# PX4FMUv2_4_6_10.net
KiCad netlist of a schematic drawn in Altium Designer
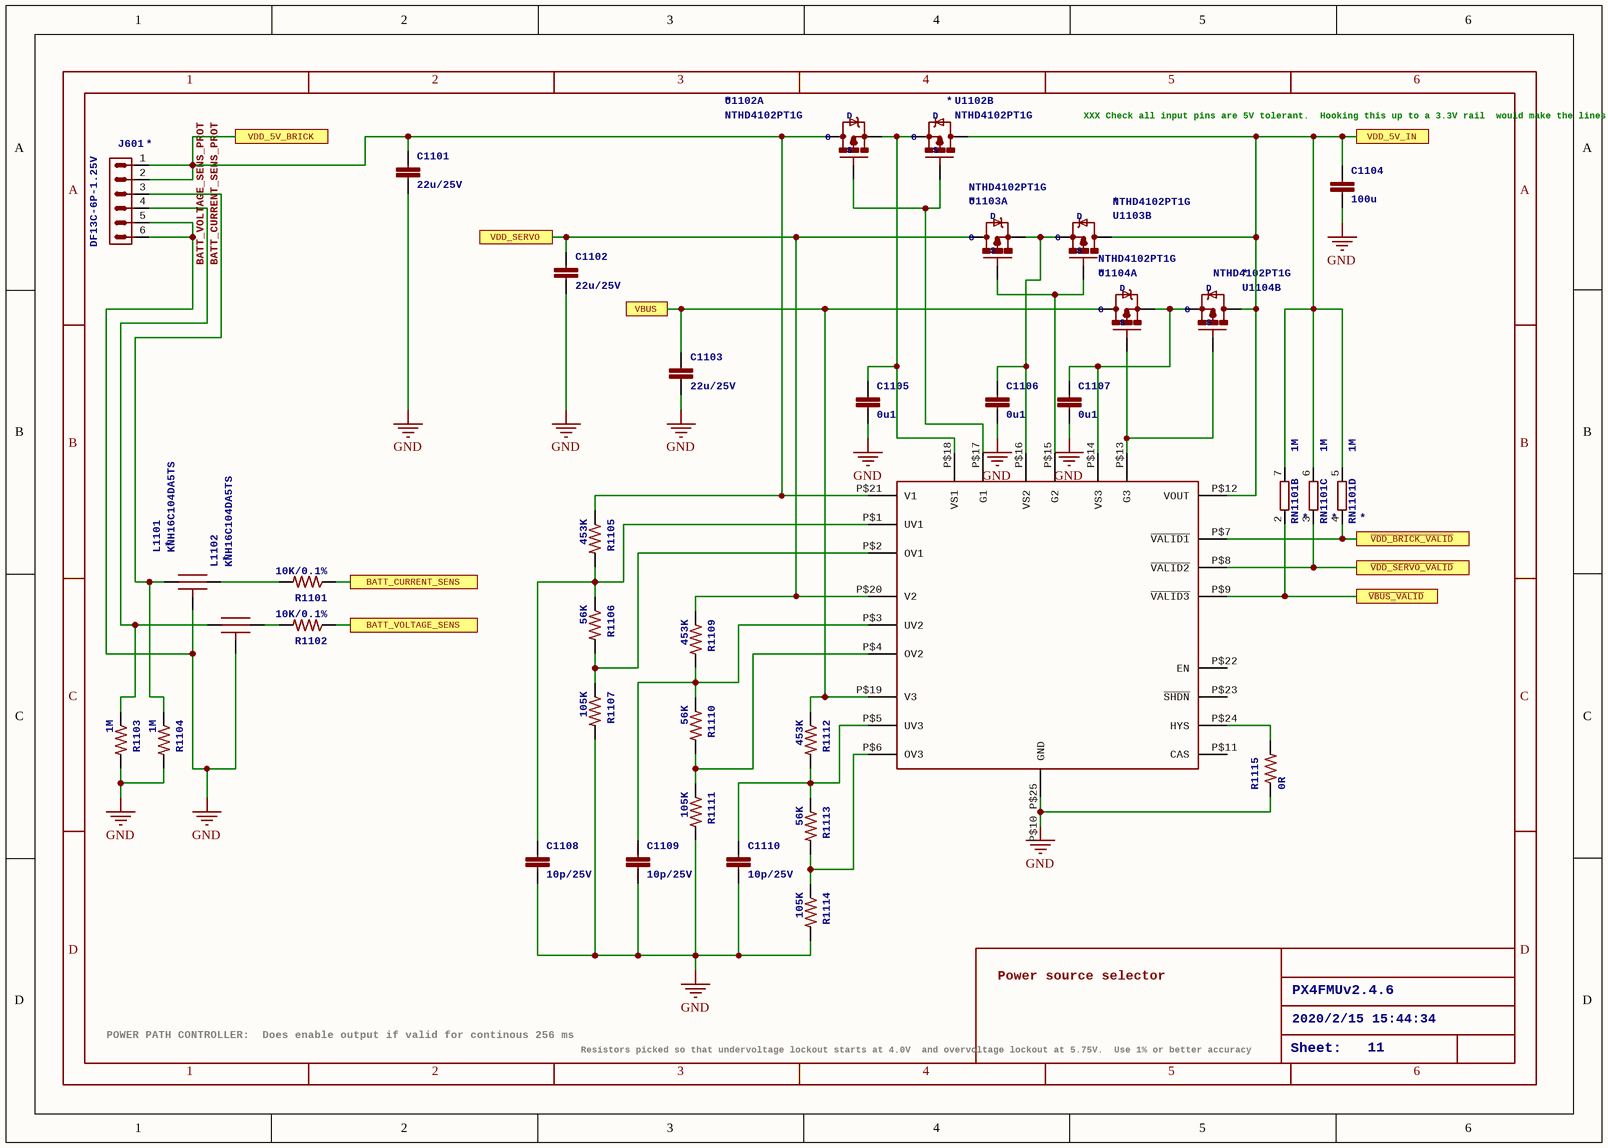
[diagram p0: PX4FMUv2.4.6_10.SchDoc]

(export (version "E")
  (design (tool "Eeschema 10.0.6"))
  (components
    (comp (ref "C1101")
      (value "22u/25V")
      (footprint "0805-CAP")
      (description "CapacitorStandard 0603 ceramic capacitor, and 0.1\" leaded capacitor.")
      (fields (field (name "PARTNO") "CL21A226MAQNNNE"))
      (libsource (lib "pixhawk2") (part "CAP0805"))
    )
    (comp (ref "C1102")
      (value "22u/25V")
      (footprint "0805-CAP")
      (description "CapacitorStandard 0603 ceramic capacitor, and 0.1\" leaded capacitor.")
      (fields (field (name "PARTNO") "CL21A226MAQNNNE"))
      (libsource (lib "pixhawk2") (part "CAP0805"))
    )
    (comp (ref "C1103")
      (value "22u/25V")
      (footprint "0805-CAP")
      (description "CapacitorStandard 0603 ceramic capacitor, and 0.1\" leaded capacitor.")
      (fields (field (name "PARTNO") "CL21A226MAQNNNE"))
      (libsource (lib "pixhawk2") (part "CAP0805"))
    )
    (comp (ref "C1104")
      (value "100u")
      (footprint "1206-CAP")
      (description "CapacitorStandard 0603 ceramic capacitor, and 0.1\" leaded capacitor.")
      (fields (field (name "PARTNO") "C3216X5R1A107M160AC"))
      (libsource (lib "pixhawk2") (part "CAP1206"))
    )
    (comp (ref "C1105")
      (value "0u1")
      (footprint "0402-CAP")
      (description "CapacitorStandard 0603 ceramic capacitor, and 0.1\" leaded capacitor.")
      (fields (field (name "PARTNO") "C1005X7R1E104K050BB"))
      (libsource (lib "pixhawk2") (part "CAP0402"))
    )
    (comp (ref "C1106")
      (value "0u1")
      (footprint "0402-CAP")
      (description "CapacitorStandard 0603 ceramic capacitor, and 0.1\" leaded capacitor.")
      (fields (field (name "PARTNO") "C1005X7R1E104K050BB"))
      (libsource (lib "pixhawk2") (part "CAP0402"))
    )
    (comp (ref "C1107")
      (value "0u1")
      (footprint "0402-CAP")
      (description "CapacitorStandard 0603 ceramic capacitor, and 0.1\" leaded capacitor.")
      (fields (field (name "PARTNO") "C1005X7R1E104K050BB"))
      (libsource (lib "pixhawk2") (part "CAP0402"))
    )
    (comp (ref "C1108")
      (value "10p/25V")
      (footprint "0402-CAP")
      (description "CapacitorStandard 0603 ceramic capacitor, and 0.1\" leaded capacitor.")
      (fields (field (name "PARTNO") "C0402C100J3GACTU"))
      (libsource (lib "pixhawk2") (part "CAP0402"))
    )
    (comp (ref "C1109")
      (value "10p/25V")
      (footprint "0402-CAP")
      (description "CapacitorStandard 0603 ceramic capacitor, and 0.1\" leaded capacitor.")
      (fields (field (name "PARTNO") "C0402C100J3GACTU"))
      (libsource (lib "pixhawk2") (part "CAP0402"))
    )
    (comp (ref "C1110")
      (value "10p/25V")
      (footprint "0402-CAP")
      (description "CapacitorStandard 0603 ceramic capacitor, and 0.1\" leaded capacitor.")
      (fields (field (name "PARTNO") "C0402C100J3GACTU"))
      (libsource (lib "pixhawk2") (part "CAP0402"))
    )
    (comp (ref "J601")
      (value "DF13C-6P-1.25V")
      (footprint "DF13C-6P-1.25V")
      (description "DF13-6P 1.25mm Pitch Miniature Crimping Connector.")
      (fields
        (field (name "NAME") "*")
        (field (name "PARTNO") "DF13C-6P-1.25V(20)")
        (field (name "LIBRARYNAME") "con-hirose-df13")
      )
      (libsource (lib "con-hirose-df13") (part "DF13-6P-1.25V"))
    )
    (comp (ref "L1101")
      (value "KNH16C104DA5TS")
      (footprint "KYOCERA-KNH16-DA")
      (description "Kyocera KNH16C104DA5TS EMI filter")
      (fields (field (name "NAME") "*"))
      (libsource (lib "pixhawk2") (part "KNH16C104DA5TS"))
    )
    (comp (ref "L1102")
      (value "KNH16C104DA5TS")
      (footprint "KYOCERA-KNH16-DA")
      (description "Kyocera KNH16C104DA5TS EMI filter")
      (fields (field (name "NAME") "*"))
      (libsource (lib "pixhawk2") (part "KNH16C104DA5TS"))
    )
    (comp (ref "R1101")
      (value "10K/0.1%")
      (footprint "0402-RES")
      (fields (field (name "PARTNO") "ERA-2AEB103X"))
      (libsource (lib "pixhawk2") (part "RESISTOR0402-RES"))
    )
    (comp (ref "R1102")
      (value "10K/0.1%")
      (footprint "0402-RES")
      (fields (field (name "PARTNO") "ERA-2AEB103X"))
      (libsource (lib "pixhawk2") (part "RESISTOR0402-RES"))
    )
    (comp (ref "R1103")
      (value "1M")
      (footprint "0402-RES")
      (fields (field (name "PARTNO") "RC0402FR-071ML"))
      (libsource (lib "pixhawk2") (part "RESISTOR0402-RES"))
    )
    (comp (ref "R1104")
      (value "1M")
      (footprint "0402-RES")
      (fields (field (name "PARTNO") "RC0402FR-071ML"))
      (libsource (lib "pixhawk2") (part "RESISTOR0402-RES"))
    )
    (comp (ref "R1105")
      (value "453K")
      (footprint "0402-RES")
      (fields (field (name "PARTNO") "RMCF0402FT453K"))
      (libsource (lib "pixhawk2") (part "RESISTOR0402-RES"))
    )
    (comp (ref "R1106")
      (value "56K")
      (footprint "0402-RES")
      (fields (field (name "PARTNO") "ERA-2AEB563X"))
      (libsource (lib "pixhawk2") (part "RESISTOR0402-RES"))
    )
    (comp (ref "R1107")
      (value "105K")
      (footprint "0402-RES")
      (fields (field (name "PARTNO") "ERJ-2RKF1053X"))
      (libsource (lib "pixhawk2") (part "RESISTOR0402-RES"))
    )
    (comp (ref "R1109")
      (value "453K")
      (footprint "0402-RES")
      (fields (field (name "PARTNO") "RMCF0402FT453K"))
      (libsource (lib "pixhawk2") (part "RESISTOR0402-RES"))
    )
    (comp (ref "R1110")
      (value "56K")
      (footprint "0402-RES")
      (fields (field (name "PARTNO") "ERA-2AEB563X"))
      (libsource (lib "pixhawk2") (part "RESISTOR0402-RES"))
    )
    (comp (ref "R1111")
      (value "105K")
      (footprint "0402-RES")
      (fields (field (name "PARTNO") "ERJ-2RKF1053X"))
      (libsource (lib "pixhawk2") (part "RESISTOR0402-RES"))
    )
    (comp (ref "R1112")
      (value "453K")
      (footprint "0402-RES")
      (fields (field (name "PARTNO") "RMCF0402FT453K"))
      (libsource (lib "pixhawk2") (part "RESISTOR0402-RES"))
    )
    (comp (ref "R1113")
      (value "56K")
      (footprint "0402-RES")
      (fields (field (name "PARTNO") "ERA-2AEB563X"))
      (libsource (lib "pixhawk2") (part "RESISTOR0402-RES"))
    )
    (comp (ref "R1114")
      (value "105K")
      (footprint "0402-RES")
      (fields (field (name "PARTNO") "ERJ-2RKF1053X"))
      (libsource (lib "pixhawk2") (part "RESISTOR0402-RES"))
    )
    (comp (ref "R1115")
      (value "0R")
      (footprint "0402-RES")
      (fields (field (name "PARTNO") "ERJ-2GE0R00X"))
      (libsource (lib "pixhawk2") (part "RESISTOR0402-RES"))
    )
    (comp (ref "RN1101")
      (value "1M")
      (footprint "EXB28V")
      (description "Array Chip ResistorSource: RS Component / Phycomp")
      (fields
        (field (name "NAME") "*")
        (field (name "PARTNO") "EXB-28V105JX")
        (field (name "LIBRARYNAME") "resistor-dil")
      )
      (libsource (lib "resistor-dil") (part "4R-NEXB28V"))
    )
    (comp (ref "U1101")
      (value "LTC4417")
      (footprint "MO-220")
      (fields (field (name "PARTNO") "LTC4417IUF#PBF"))
      (libsource (lib "pixhawk2") (part "LTC4117"))
    )
    (comp (ref "U1102")
      (value "NTHD4102PT1G")
      (footprint "1206-8")
      (fields (field (name "NAME") "*") (field (name "D") "D") (field (name "S") "S") (field (name "G") "G"))
      (libsource (lib "") (part "MOSFET-DUAL-PCHANNEL-CHIPFET_1"))
    )
    (comp (ref "U1103")
      (value "NTHD4102PT1G")
      (footprint "1206-8")
      (fields (field (name "NAME") "*") (field (name "D") "D") (field (name "S") "S") (field (name "G") "G"))
      (libsource (lib "") (part "MOSFET-DUAL-PCHANNEL-CHIPFET_1"))
    )
    (comp (ref "U1104")
      (value "NTHD4102PT1G")
      (footprint "1206-8")
      (fields (field (name "NAME") "*") (field (name "D") "D") (field (name "S") "S") (field (name "G") "G"))
      (libsource (lib "pixhawk2") (part "MOSFET-DUAL-PCHANNEL-CHIPFET"))
    )
  )
  (nets
    (net (code "1") (name "/BATT_CURRENT_SENS") (class "Default")
      (node (ref "R1101") (pin "P$1") (pinfunction "1_P$1") (pintype "passive"))
    )
    (net (code "2") (name "/BATT_CURRENT_SENS_PROT") (class "Default")
      (node (ref "J601") (pin "3") (pinfunction "3_3") (pintype "passive"))
      (node (ref "L1101") (pin "P$1") (pinfunction "P$1_P$1") (pintype "passive"))
      (node (ref "R1104") (pin "P$1") (pinfunction "1_P$1") (pintype "passive"))
    )
    (net (code "3") (name "/BATT_VOLTAGE_SENS") (class "Default")
      (node (ref "R1102") (pin "P$1") (pinfunction "1_P$1") (pintype "passive"))
    )
    (net (code "4") (name "/BATT_VOLTAGE_SENS_PROT") (class "Default")
      (node (ref "J601") (pin "4") (pinfunction "4_4") (pintype "passive"))
      (node (ref "L1102") (pin "P$1") (pinfunction "P$1_P$1") (pintype "passive"))
      (node (ref "R1103") (pin "P$1") (pinfunction "1_P$1") (pintype "passive"))
    )
    (net (code "5") (name "/VBUS") (class "Default")
      (node (ref "C1103") (pin "P$1") (pinfunction "1_P$1") (pintype "passive"))
      (node (ref "R1112") (pin "P$1") (pinfunction "1_P$1") (pintype "passive"))
      (node (ref "U1101") (pin "P$19") (pinfunction "V3_P$19") (pintype "passive"))
      (node (ref "U1104") (pin "P$7_P$8") (pinfunction "D_P$7_P$8") (pintype "passive"))
    )
    (net (code "6") (name "/VDD_5V_BRICK") (class "Default")
      (node (ref "C1101") (pin "P$1") (pinfunction "1_P$1") (pintype "passive"))
      (node (ref "J601") (pin "1") (pinfunction "1_1") (pintype "passive"))
      (node (ref "J601") (pin "2") (pinfunction "2_2") (pintype "passive"))
      (node (ref "R1105") (pin "P$1") (pinfunction "1_P$1") (pintype "passive"))
      (node (ref "U1101") (pin "P$21") (pinfunction "V1_P$21") (pintype "passive"))
      (node (ref "U1102") (pin "P$7_P$8") (pinfunction "D_P$7_P$8") (pintype "passive"))
    )
    (net (code "7") (name "/VDD_5V_IN") (class "Default")
      (node (ref "C1104") (pin "P$1") (pinfunction "1_P$1") (pintype "passive"))
      (node (ref "RN1101") (pin "5") (pinfunction "2_5") (pintype "passive"))
      (node (ref "RN1101") (pin "6") (pinfunction "2_6") (pintype "passive"))
      (node (ref "RN1101") (pin "7") (pinfunction "2_7") (pintype "passive"))
      (node (ref "U1101") (pin "P$12") (pinfunction "VOUT_P$12") (pintype "passive"))
      (node (ref "U1102") (pin "P$5_P$6") (pinfunction "D_P$5_P$6") (pintype "passive"))
      (node (ref "U1103") (pin "P$5_P$6") (pinfunction "D_P$5_P$6") (pintype "passive"))
      (node (ref "U1104") (pin "P$5_P$6") (pinfunction "D_P$5_P$6") (pintype "passive"))
    )
    (net (code "8") (name "/VDD_SERVO") (class "Default")
      (node (ref "C1102") (pin "P$1") (pinfunction "1_P$1") (pintype "passive"))
      (node (ref "R1109") (pin "P$1") (pinfunction "1_P$1") (pintype "passive"))
      (node (ref "U1101") (pin "P$20") (pinfunction "V2_P$20") (pintype "passive"))
      (node (ref "U1103") (pin "P$7_P$8") (pinfunction "D_P$7_P$8") (pintype "passive"))
    )
    (net (code "9") (name "/~{VBUS_VALID}") (class "Default")
      (node (ref "RN1101") (pin "2") (pinfunction "1_2") (pintype "passive"))
      (node (ref "U1101") (pin "P$9") (pinfunction "~{VALID3}_P$9") (pintype "passive"))
    )
    (net (code "10") (name "/~{VDD_BRICK_VALID}") (class "Default")
      (node (ref "RN1101") (pin "4") (pinfunction "1_4") (pintype "passive"))
      (node (ref "U1101") (pin "P$7") (pinfunction "~{VALID1}_P$7") (pintype "passive"))
    )
    (net (code "11") (name "/~{VDD_SERVO_VALID}") (class "Default")
      (node (ref "RN1101") (pin "3") (pinfunction "1_3") (pintype "passive"))
      (node (ref "U1101") (pin "P$8") (pinfunction "~{VALID2}_P$8") (pintype "passive"))
    )
    (net (code "12") (name "GND") (class "Default")
      (node (ref "C1101") (pin "P$2") (pinfunction "2_P$2") (pintype "passive"))
      (node (ref "C1102") (pin "P$2") (pinfunction "2_P$2") (pintype "passive"))
      (node (ref "C1103") (pin "P$2") (pinfunction "2_P$2") (pintype "passive"))
      (node (ref "C1104") (pin "P$2") (pinfunction "2_P$2") (pintype "passive"))
      (node (ref "C1105") (pin "P$2") (pinfunction "2_P$2") (pintype "passive"))
      (node (ref "C1106") (pin "P$2") (pinfunction "2_P$2") (pintype "passive"))
      (node (ref "C1107") (pin "P$2") (pinfunction "2_P$2") (pintype "passive"))
      (node (ref "C1108") (pin "P$2") (pinfunction "2_P$2") (pintype "passive"))
      (node (ref "C1109") (pin "P$2") (pinfunction "2_P$2") (pintype "passive"))
      (node (ref "C1110") (pin "P$2") (pinfunction "2_P$2") (pintype "passive"))
      (node (ref "J601") (pin "5") (pinfunction "5_5") (pintype "passive"))
      (node (ref "J601") (pin "6") (pinfunction "6_6") (pintype "passive"))
      (node (ref "L1101") (pin "P$3_P$4_P$5") (pinfunction "P$3_P$3_P$4_P$5") (pintype "passive"))
      (node (ref "L1102") (pin "P$3_P$4_P$5") (pinfunction "P$3_P$3_P$4_P$5") (pintype "passive"))
      (node (ref "R1103") (pin "P$2") (pinfunction "2_P$2") (pintype "passive"))
      (node (ref "R1104") (pin "P$2") (pinfunction "2_P$2") (pintype "passive"))
      (node (ref "R1107") (pin "P$2") (pinfunction "2_P$2") (pintype "passive"))
      (node (ref "R1111") (pin "P$2") (pinfunction "2_P$2") (pintype "passive"))
      (node (ref "R1114") (pin "P$2") (pinfunction "2_P$2") (pintype "passive"))
      (node (ref "R1115") (pin "P$1") (pinfunction "1_P$1") (pintype "passive"))
      (node (ref "U1101") (pin "P$10_P$25") (pinfunction "GND_P$10_P$25") (pintype "passive"))
    )
    (net (code "13") (name "Net-(C1105-1)") (class "Default")
      (node (ref "C1105") (pin "P$1") (pinfunction "1_P$1") (pintype "passive"))
      (node (ref "U1101") (pin "P$18") (pinfunction "VS1_P$18") (pintype "passive"))
      (node (ref "U1102") (pin "P$1") (pinfunction "S_P$1") (pintype "passive"))
      (node (ref "U1102") (pin "P$3") (pinfunction "S_P$3") (pintype "passive"))
    )
    (net (code "14") (name "Net-(C1106-1)") (class "Default")
      (node (ref "C1106") (pin "P$1") (pinfunction "1_P$1") (pintype "passive"))
      (node (ref "U1101") (pin "P$16") (pinfunction "VS2_P$16") (pintype "passive"))
      (node (ref "U1103") (pin "P$1") (pinfunction "S_P$1") (pintype "passive"))
      (node (ref "U1103") (pin "P$3") (pinfunction "S_P$3") (pintype "passive"))
    )
    (net (code "15") (name "Net-(C1107-1)") (class "Default")
      (node (ref "C1107") (pin "P$1") (pinfunction "1_P$1") (pintype "passive"))
      (node (ref "U1101") (pin "P$14") (pinfunction "VS3_P$14") (pintype "passive"))
      (node (ref "U1104") (pin "P$1") (pinfunction "S_P$1") (pintype "passive"))
      (node (ref "U1104") (pin "P$3") (pinfunction "S_P$3") (pintype "passive"))
    )
    (net (code "16") (name "Net-(C1108-1)") (class "Default")
      (node (ref "C1108") (pin "P$1") (pinfunction "1_P$1") (pintype "passive"))
      (node (ref "R1105") (pin "P$2") (pinfunction "2_P$2") (pintype "passive"))
      (node (ref "R1106") (pin "P$1") (pinfunction "1_P$1") (pintype "passive"))
      (node (ref "U1101") (pin "P$1") (pinfunction "UV1_P$1") (pintype "passive"))
    )
    (net (code "17") (name "Net-(C1109-1)") (class "Default")
      (node (ref "C1109") (pin "P$1") (pinfunction "1_P$1") (pintype "passive"))
      (node (ref "R1109") (pin "P$2") (pinfunction "2_P$2") (pintype "passive"))
      (node (ref "R1110") (pin "P$1") (pinfunction "1_P$1") (pintype "passive"))
      (node (ref "U1101") (pin "P$3") (pinfunction "UV2_P$3") (pintype "passive"))
    )
    (net (code "18") (name "Net-(C1110-1)") (class "Default")
      (node (ref "C1110") (pin "P$1") (pinfunction "1_P$1") (pintype "passive"))
      (node (ref "R1112") (pin "P$2") (pinfunction "2_P$2") (pintype "passive"))
      (node (ref "R1113") (pin "P$1") (pinfunction "1_P$1") (pintype "passive"))
      (node (ref "U1101") (pin "P$5") (pinfunction "UV3_P$5") (pintype "passive"))
    )
    (net (code "19") (name "Net-(R1101-2)") (class "Default")
      (node (ref "L1101") (pin "P$2") (pinfunction "P$2_P$2") (pintype "passive"))
      (node (ref "R1101") (pin "P$2") (pinfunction "2_P$2") (pintype "passive"))
    )
    (net (code "20") (name "Net-(R1102-2)") (class "Default")
      (node (ref "L1102") (pin "P$2") (pinfunction "P$2_P$2") (pintype "passive"))
      (node (ref "R1102") (pin "P$2") (pinfunction "2_P$2") (pintype "passive"))
    )
    (net (code "21") (name "Net-(R1106-2)") (class "Default")
      (node (ref "R1106") (pin "P$2") (pinfunction "2_P$2") (pintype "passive"))
      (node (ref "R1107") (pin "P$1") (pinfunction "1_P$1") (pintype "passive"))
      (node (ref "U1101") (pin "P$2") (pinfunction "OV1_P$2") (pintype "passive"))
    )
    (net (code "22") (name "Net-(R1110-2)") (class "Default")
      (node (ref "R1110") (pin "P$2") (pinfunction "2_P$2") (pintype "passive"))
      (node (ref "R1111") (pin "P$1") (pinfunction "1_P$1") (pintype "passive"))
      (node (ref "U1101") (pin "P$4") (pinfunction "OV2_P$4") (pintype "passive"))
    )
    (net (code "23") (name "Net-(R1113-2)") (class "Default")
      (node (ref "R1113") (pin "P$2") (pinfunction "2_P$2") (pintype "passive"))
      (node (ref "R1114") (pin "P$1") (pinfunction "1_P$1") (pintype "passive"))
      (node (ref "U1101") (pin "P$6") (pinfunction "OV3_P$6") (pintype "passive"))
    )
    (net (code "24") (name "Net-(R1115-2)") (class "Default")
      (node (ref "R1115") (pin "P$2") (pinfunction "2_P$2") (pintype "passive"))
      (node (ref "U1101") (pin "P$24") (pinfunction "HYS_P$24") (pintype "passive"))
    )
    (net (code "25") (name "Net-(U1101-G1)") (class "Default")
      (node (ref "U1101") (pin "P$17") (pinfunction "G1_P$17") (pintype "passive"))
      (node (ref "U1102") (pin "P$2") (pinfunction "G_P$2") (pintype "passive"))
      (node (ref "U1102") (pin "P$4") (pinfunction "G_P$4") (pintype "passive"))
    )
    (net (code "26") (name "Net-(U1101-G2)") (class "Default")
      (node (ref "U1101") (pin "P$15") (pinfunction "G2_P$15") (pintype "passive"))
      (node (ref "U1103") (pin "P$2") (pinfunction "G_P$2") (pintype "passive"))
      (node (ref "U1103") (pin "P$4") (pinfunction "G_P$4") (pintype "passive"))
    )
    (net (code "27") (name "Net-(U1101-G3)") (class "Default")
      (node (ref "U1101") (pin "P$13") (pinfunction "G3_P$13") (pintype "passive"))
      (node (ref "U1104") (pin "P$2") (pinfunction "G_P$2") (pintype "passive"))
      (node (ref "U1104") (pin "P$4") (pinfunction "G_P$4") (pintype "passive"))
    )
    (net (code "28") (name "unconnected-(U1101-CAS-PadP$11)") (class "Default")
      (node (ref "U1101") (pin "P$11") (pinfunction "CAS_P$11") (pintype "passive"))
    )
    (net (code "29") (name "unconnected-(U1101-EN-PadP$22)") (class "Default")
      (node (ref "U1101") (pin "P$22") (pinfunction "EN_P$22") (pintype "passive"))
    )
    (net (code "30") (name "unconnected-(U1101-~{SHDN}-PadP$23)") (class "Default")
      (node (ref "U1101") (pin "P$23") (pinfunction "~{SHDN}_P$23") (pintype "passive"))
    )
  )
)
